# OZ440-SE110-CAR001-SCH3.net
KiCad netlist of a schematic drawn in Altium Designer
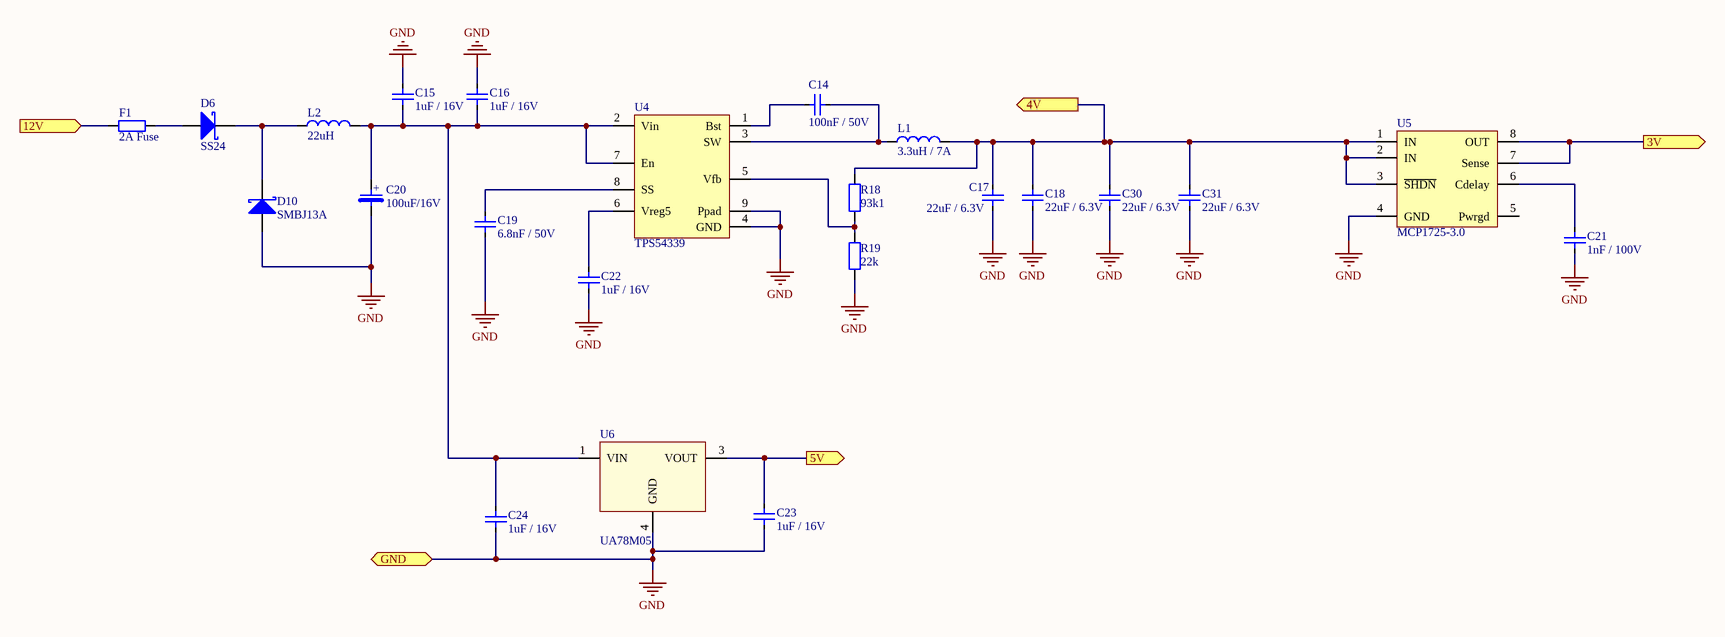
[diagram p0: OZ440-SE110-CAR001-SCH3.SchDoc]

(export (version "E")
  (design (tool "Eeschema 10.0.6"))
  (components
    (comp (ref "C14")
      (value "CAP-SMD")
      (footprint "C0805-STD")
      (description "0805 100nF / 50V  X7R ceramic capacitor")
      (fields
        (field (name "DISPLAYED REFERENCE") "100nF / 50V")
        (field (name "TOLERANCE") "+/- 10%")
        (field (name "MANUFACTURER") "vishay")
      )
      (libsource (lib "lib_NAIO") (part "CAP-SMD"))
    )
    (comp (ref "C15")
      (value "CAP-SMD")
      (footprint "C0805-STD")
      (description "0805 1uF / 16V X7R ceramic capacitor")
      (fields
        (field (name "DISPLAYED REFERENCE") "1uF / 16V")
        (field (name "TOLERANCE") "+/- 10%")
        (field (name "MANUFACTURER") "Kemet")
      )
      (libsource (lib "lib_NAIO") (part "CAP-SMD"))
    )
    (comp (ref "C16")
      (value "CAP-SMD")
      (footprint "C0805-STD")
      (description "0805 1uF / 16V X7R ceramic capacitor")
      (fields
        (field (name "DISPLAYED REFERENCE") "1uF / 16V")
        (field (name "TOLERANCE") "+/- 10%")
        (field (name "MANUFACTURER") "Kemet")
      )
      (libsource (lib "lib_NAIO") (part "CAP-SMD"))
    )
    (comp (ref "C17")
      (value "CAP-SMD")
      (footprint "C0805-STD")
      (description "0805 22uF / 6.3V X5R ceramic capacitor")
      (fields
        (field (name "DISPLAYED REFERENCE") "22uF / 6.3V")
        (field (name "TOLERANCE") "+/- 20%")
        (field (name "MANUFACTURER") "Kemet")
      )
      (libsource (lib "lib_NAIO") (part "CAP-SMD"))
    )
    (comp (ref "C18")
      (value "CAP-SMD")
      (footprint "C0805-STD")
      (description "0805 22uF / 6.3V X5R ceramic capacitor")
      (fields
        (field (name "DISPLAYED REFERENCE") "22uF / 6.3V")
        (field (name "TOLERANCE") "+/- 20%")
        (field (name "MANUFACTURER") "Kemet")
      )
      (libsource (lib "lib_NAIO") (part "CAP-SMD"))
    )
    (comp (ref "C19")
      (value "CAP-SMD")
      (footprint "C0805-STD")
      (description "0805 6.8nF / 50V COG ceramic capacitor")
      (fields
        (field (name "DISPLAYED REFERENCE") "6.8nF / 50V")
        (field (name "TOLERANCE") "+/- 5%")
        (field (name "MANUFACTURER") "Kemet")
      )
      (libsource (lib "lib_NAIO") (part "CAP-SMD"))
    )
    (comp (ref "C20")
      (value "CAP-POL-SMD")
      (footprint "CAP-ELECTRO-SMD")
      (description "100uF/16V Aluminium capacitor SMD")
      (fields (field (name "DISPLAYED REFERENCE") "100uF/16V") (field (name "MANUFACTURER") "Epcos"))
      (libsource (lib "lib_NAIO") (part "CAP-POL-SMD"))
    )
    (comp (ref "C21")
      (value "CAP-SMD")
      (footprint "C0805-STD")
      (description "0805 1nF / 100V X7R ceramic capacitor")
      (fields
        (field (name "DISPLAYED REFERENCE") "1nF / 100V")
        (field (name "TOLERANCE") "+/- 10%")
        (field (name "MANUFACTURER") "vishay")
      )
      (libsource (lib "lib_NAIO") (part "CAP-SMD"))
    )
    (comp (ref "C22")
      (value "CAP-SMD")
      (footprint "C0805-STD")
      (description "0805 1uF / 16V X7R ceramic capacitor")
      (fields
        (field (name "DISPLAYED REFERENCE") "1uF / 16V")
        (field (name "TOLERANCE") "+/- 10%")
        (field (name "MANUFACTURER") "Kemet")
      )
      (libsource (lib "lib_NAIO") (part "CAP-SMD"))
    )
    (comp (ref "C23")
      (value "CAP-SMD")
      (footprint "C0805-STD")
      (description "0805 1uF / 16V X7R ceramic capacitor")
      (fields
        (field (name "DISPLAYED REFERENCE") "1uF / 16V")
        (field (name "TOLERANCE") "+/- 10%")
        (field (name "MANUFACTURER") "Kemet")
      )
      (libsource (lib "lib_NAIO") (part "CAP-SMD"))
    )
    (comp (ref "C24")
      (value "CAP-SMD")
      (footprint "C0805-STD")
      (description "0805 1uF / 16V X7R ceramic capacitor")
      (fields
        (field (name "DISPLAYED REFERENCE") "1uF / 16V")
        (field (name "TOLERANCE") "+/- 10%")
        (field (name "MANUFACTURER") "Kemet")
      )
      (libsource (lib "lib_NAIO") (part "CAP-SMD"))
    )
    (comp (ref "C30")
      (value "CAP-SMD")
      (footprint "C0805-STD")
      (description "0805 22uF / 6.3V X5R ceramic capacitor")
      (fields
        (field (name "DISPLAYED REFERENCE") "22uF / 6.3V")
        (field (name "TOLERANCE") "+/- 20%")
        (field (name "MANUFACTURER") "Kemet")
      )
      (libsource (lib "lib_NAIO") (part "CAP-SMD"))
    )
    (comp (ref "C31")
      (value "CAP-SMD")
      (footprint "C0805-STD")
      (description "0805 22uF / 6.3V X5R ceramic capacitor")
      (fields
        (field (name "DISPLAYED REFERENCE") "22uF / 6.3V")
        (field (name "TOLERANCE") "+/- 20%")
        (field (name "MANUFACTURER") "Kemet")
      )
      (libsource (lib "lib_NAIO") (part "CAP-SMD"))
    )
    (comp (ref "D6")
      (value "DIODE_SCHOTKY-DO214AA")
      (footprint "DO214AA-STD")
      (description "2A/40V schottky diode in SMB package")
      (fields (field (name "DISPLAYED REFERENCE") "SS24") (field (name "MANUFACTURER") "VISHAY"))
      (libsource (lib "lib_NAIO") (part "DIODE_SCHOTKY-DO214AA"))
    )
    (comp (ref "D10")
      (value "DIODE_SCHOTKY-DO214AA")
      (footprint "DO214AA-STD")
      (description "13V TVS diode, 600W")
      (fields (field (name "DISPLAYED REFERENCE") "SMBJ13A") (field (name "MANUFACTURER") "LITTLEFUSE"))
      (libsource (lib "lib_NAIO") (part "DIODE_SCHOTKY-DO214AA"))
    )
    (comp (ref "F1")
      (value "RES-SMD")
      (footprint "R0805-STD")
      (description "0805 2A 63V fuse")
      (fields (field (name "DISPLAYED REFERENCE") "2A Fuse") (field (name "MANUFACTURER") "AVX"))
      (libsource (lib "lib_NAIO") (part "RES-SMD"))
    )
    (comp (ref "L1")
      (value "IND-SMD")
      (footprint "L-SPE-EPL6024")
      (description "3.3uH 7A SMD inductor")
      (fields (field (name "DISPLAYED REFERENCE") "3.3uH / 7A") (field (name "MANUFACTURER") "COILCRAFT"))
      (libsource (lib "lib_NAIO") (part "IND-SMD"))
    )
    (comp (ref "L2")
      (value "IND-SMD")
      (footprint "L-SPE-LPS6235")
      (description "22uH SMD inductor")
      (fields (field (name "DISPLAYED REFERENCE") "22uH") (field (name "MANUFACTURER") "Coilcraft"))
      (libsource (lib "lib_NAIO") (part "IND-SMD"))
    )
    (comp (ref "R18")
      (value "RES-SMD")
      (footprint "R0805-STD")
      (description "93k1 Ohm 0805 SMD resistor")
      (fields
        (field (name "DISPLAYED REFERENCE") "93k1")
        (field (name "TOLERANCE") "1%")
        (field (name "MANUFACTURER") "Vishay")
      )
      (libsource (lib "") (part "RES-SMD_1"))
    )
    (comp (ref "R19")
      (value "RES-SMD")
      (footprint "R0805-STD")
      (description "22k Ohm 0805 SMD resistor")
      (fields
        (field (name "DISPLAYED REFERENCE") "22k")
        (field (name "TOLERANCE") "1 %")
        (field (name "MANUFACTURER") "Vishay")
      )
      (libsource (lib "") (part "RES-SMD_1"))
    )
    (comp (ref "U4")
      (value "TPS54339-SO8")
      (footprint "SO8_THERMAL-STD")
      (description "4.5 V to 23 V Input, 3-A Step-Down DCDC")
      (fields (field (name "DISPLAYED REFERENCE") "TPS54339") (field (name "MANUFACTURER") "TI"))
      (libsource (lib "lib_NAIO") (part "TPS54339-SO8"))
    )
    (comp (ref "U5")
      (value "MCP1725-SO8")
      (footprint "SO8-STD")
      (description "low drop, 3V linear regulator")
      (fields (field (name "DISPLAYED REFERENCE") "MCP1725-3.0") (field (name "MANUFACTURER") "Microchip"))
      (libsource (lib "lib_NAIO") (part "MCP1725-SO8"))
    )
    (comp (ref "U6")
      (value "uA78MXX-TO252")
      (footprint "TO252-SPE-UA78Mxx")
      (description "5V / 500mA linear regulator")
      (fields (field (name "DISPLAYED REFERENCE") "UA78M05") (field (name "MANUFACTURER") "TI"))
      (libsource (lib "lib_NAIO") (part "uA78MXX-TO252"))
    )
  )
  (nets
    (net (code "1") (name "/3V") (class "Default")
      (node (ref "U5") (pin "7") (pinfunction "Sense_7") (pintype "passive"))
      (node (ref "U5") (pin "8") (pinfunction "OUT_8") (pintype "passive"))
    )
    (net (code "2") (name "/4V") (class "Default")
      (node (ref "C17") (pin "2") (pinfunction "2_2") (pintype "passive"))
      (node (ref "C18") (pin "2") (pinfunction "2_2") (pintype "passive"))
      (node (ref "C30") (pin "2") (pinfunction "2_2") (pintype "passive"))
      (node (ref "C31") (pin "2") (pinfunction "2_2") (pintype "passive"))
      (node (ref "L1") (pin "2") (pinfunction "2_2") (pintype "passive"))
      (node (ref "R18") (pin "2") (pinfunction "2_2") (pintype "passive"))
      (node (ref "U5") (pin "1") (pinfunction "IN_1") (pintype "passive"))
      (node (ref "U5") (pin "2") (pinfunction "IN_2") (pintype "passive"))
      (node (ref "U5") (pin "3") (pinfunction "~{SHDN}_3") (pintype "passive"))
    )
    (net (code "3") (name "/5V") (class "Default")
      (node (ref "C23") (pin "2") (pinfunction "2_2") (pintype "passive"))
      (node (ref "U6") (pin "3") (pinfunction "VOUT_3") (pintype "passive"))
    )
    (net (code "4") (name "/12V") (class "Default")
      (node (ref "F1") (pin "1") (pinfunction "1_1") (pintype "passive"))
    )
    (net (code "5") (name "GND") (class "Default")
      (node (ref "C15") (pin "2") (pinfunction "2_2") (pintype "passive"))
      (node (ref "C16") (pin "2") (pinfunction "2_2") (pintype "passive"))
      (node (ref "C17") (pin "1") (pinfunction "1_1") (pintype "passive"))
      (node (ref "C18") (pin "1") (pinfunction "1_1") (pintype "passive"))
      (node (ref "C19") (pin "1") (pinfunction "1_1") (pintype "passive"))
      (node (ref "C20") (pin "2") (pinfunction "2_2") (pintype "passive"))
      (node (ref "C21") (pin "1") (pinfunction "1_1") (pintype "passive"))
      (node (ref "C22") (pin "1") (pinfunction "1_1") (pintype "passive"))
      (node (ref "C23") (pin "1") (pinfunction "1_1") (pintype "passive"))
      (node (ref "C24") (pin "1") (pinfunction "1_1") (pintype "passive"))
      (node (ref "C30") (pin "1") (pinfunction "1_1") (pintype "passive"))
      (node (ref "C31") (pin "1") (pinfunction "1_1") (pintype "passive"))
      (node (ref "D10") (pin "A") (pinfunction "A_A") (pintype "passive"))
      (node (ref "R19") (pin "1") (pinfunction "1_1") (pintype "passive"))
      (node (ref "U4") (pin "4") (pinfunction "GND_4") (pintype "passive"))
      (node (ref "U4") (pin "9") (pinfunction "Ppad_9") (pintype "passive"))
      (node (ref "U5") (pin "4") (pinfunction "GND_4") (pintype "passive"))
      (node (ref "U6") (pin "4") (pinfunction "GND_4") (pintype "passive"))
    )
    (net (code "6") (name "Net-(D6-PadA)") (class "Default")
      (node (ref "D6") (pin "A") (pinfunction "A_A") (pintype "passive"))
      (node (ref "F1") (pin "2") (pinfunction "2_2") (pintype "passive"))
    )
    (net (code "7") (name "Net-(D10-PadK)") (class "Default")
      (node (ref "D10") (pin "K") (pinfunction "K_K") (pintype "passive"))
      (node (ref "D6") (pin "K") (pinfunction "K_K") (pintype "passive"))
      (node (ref "L2") (pin "1") (pinfunction "1_1") (pintype "passive"))
    )
    (net (code "8") (name "Net-(U4-Bst)") (class "Default")
      (node (ref "C14") (pin "1") (pinfunction "1_1") (pintype "passive"))
      (node (ref "U4") (pin "1") (pinfunction "Bst_1") (pintype "passive"))
    )
    (net (code "9") (name "Net-(U4-En)") (class "Default")
      (node (ref "C15") (pin "1") (pinfunction "1_1") (pintype "passive"))
      (node (ref "C16") (pin "1") (pinfunction "1_1") (pintype "passive"))
      (node (ref "C20") (pin "1") (pinfunction "1_1") (pintype "passive"))
      (node (ref "C24") (pin "2") (pinfunction "2_2") (pintype "passive"))
      (node (ref "L2") (pin "2") (pinfunction "2_2") (pintype "passive"))
      (node (ref "U4") (pin "2") (pinfunction "Vin_2") (pintype "passive"))
      (node (ref "U4") (pin "7") (pinfunction "En_7") (pintype "passive"))
      (node (ref "U6") (pin "1") (pinfunction "VIN_1") (pintype "passive"))
    )
    (net (code "10") (name "Net-(U4-SS)") (class "Default")
      (node (ref "C19") (pin "2") (pinfunction "2_2") (pintype "passive"))
      (node (ref "U4") (pin "8") (pinfunction "SS_8") (pintype "passive"))
    )
    (net (code "11") (name "Net-(U4-SW)") (class "Default")
      (node (ref "C14") (pin "2") (pinfunction "2_2") (pintype "passive"))
      (node (ref "L1") (pin "1") (pinfunction "1_1") (pintype "passive"))
      (node (ref "U4") (pin "3") (pinfunction "SW_3") (pintype "passive"))
    )
    (net (code "12") (name "Net-(U4-Vfb)") (class "Default")
      (node (ref "R18") (pin "1") (pinfunction "1_1") (pintype "passive"))
      (node (ref "R19") (pin "2") (pinfunction "2_2") (pintype "passive"))
      (node (ref "U4") (pin "5") (pinfunction "Vfb_5") (pintype "passive"))
    )
    (net (code "13") (name "Net-(U4-Vreg5)") (class "Default")
      (node (ref "C22") (pin "2") (pinfunction "2_2") (pintype "passive"))
      (node (ref "U4") (pin "6") (pinfunction "Vreg5_6") (pintype "passive"))
    )
    (net (code "14") (name "Net-(U5-Cdelay)") (class "Default")
      (node (ref "C21") (pin "2") (pinfunction "2_2") (pintype "passive"))
      (node (ref "U5") (pin "6") (pinfunction "Cdelay_6") (pintype "passive"))
    )
    (net (code "15") (name "unconnected-(U5-Pwrgd-Pad5)") (class "Default")
      (node (ref "U5") (pin "5") (pinfunction "Pwrgd_5") (pintype "passive"))
    )
  )
)
